# bbtc-relays.net
KiCad netlist of a schematic drawn in EAGLE
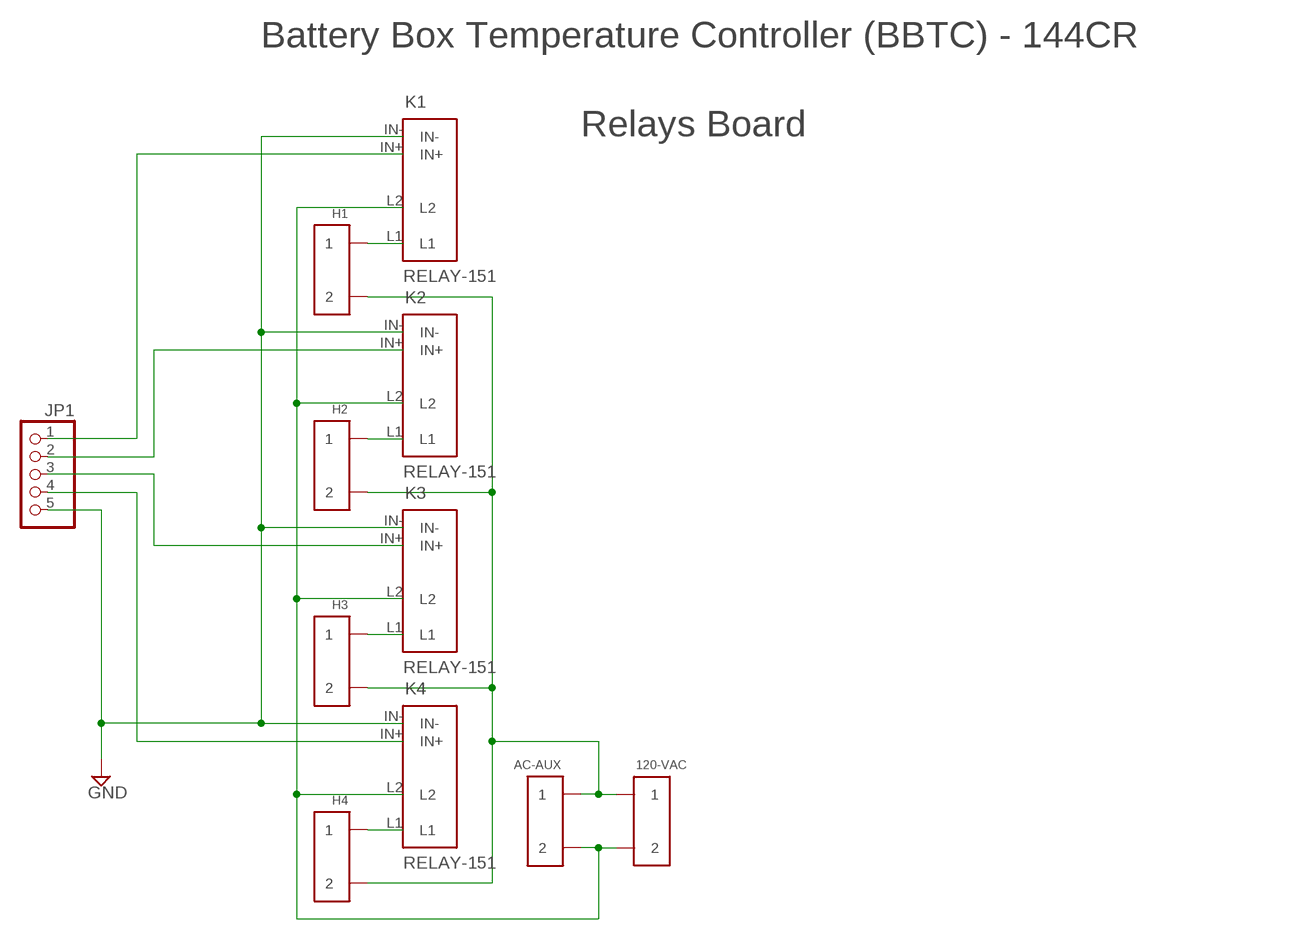
[diagram p0: schematic, sheet 1]

(export (version "E")
  (design (tool "Eeschema 10.0.6"))
  (components
    (comp (ref "120-VAC")
      (value "SCREW-CLAMP-906")
      (footprint "eagle-import:SCREW-CLAMP-906")
      (libsource (lib "eagle-import") (part "SCREW-CLAMP-906"))
    )
    (comp (ref "AC-AUX")
      (value "SCREW-CLAMP-909")
      (footprint "eagle-import:SCREW-CLAMP-909")
      (libsource (lib "eagle-import") (part "SCREW-CLAMP-909"))
    )
    (comp (ref "H1")
      (value "SCREW-CLAMP-906")
      (footprint "eagle-import:SCREW-CLAMP-906")
      (libsource (lib "eagle-import") (part "SCREW-CLAMP-906"))
    )
    (comp (ref "H2")
      (value "SCREW-CLAMP-906")
      (footprint "eagle-import:SCREW-CLAMP-906")
      (libsource (lib "eagle-import") (part "SCREW-CLAMP-906"))
    )
    (comp (ref "H3")
      (value "SCREW-CLAMP-906")
      (footprint "eagle-import:SCREW-CLAMP-906")
      (libsource (lib "eagle-import") (part "SCREW-CLAMP-906"))
    )
    (comp (ref "H4")
      (value "SCREW-CLAMP-906")
      (footprint "eagle-import:SCREW-CLAMP-906")
      (libsource (lib "eagle-import") (part "SCREW-CLAMP-906"))
    )
    (comp (ref "JP1")
      (value "PINHD-1X5")
      (footprint "eagle-import:1X05")
      (libsource (lib "eagle-import") (part "PINHD-1X5"))
    )
    (comp (ref "K1")
      (value "RELAY-151")
      (footprint "eagle-import:RELAY-151")
      (libsource (lib "eagle-import") (part "RELAY-151"))
    )
    (comp (ref "K2")
      (value "RELAY-151")
      (footprint "eagle-import:RELAY-151")
      (libsource (lib "eagle-import") (part "RELAY-151"))
    )
    (comp (ref "K3")
      (value "RELAY-151")
      (footprint "eagle-import:RELAY-151")
      (libsource (lib "eagle-import") (part "RELAY-151"))
    )
    (comp (ref "K4")
      (value "RELAY-151")
      (footprint "eagle-import:RELAY-151")
      (libsource (lib "eagle-import") (part "RELAY-151"))
    )
  )
  (nets
    (net (code "1") (name "GND") (class "Default")
      (node (ref "JP1") (pin "5") (pinfunction "5_5") (pintype "passive"))
      (node (ref "K1") (pin "IN-") (pinfunction "IN-_IN-") (pintype "bidirectional"))
      (node (ref "K2") (pin "IN-") (pinfunction "IN-_IN-") (pintype "bidirectional"))
      (node (ref "K3") (pin "IN-") (pinfunction "IN-_IN-") (pintype "bidirectional"))
      (node (ref "K4") (pin "IN-") (pinfunction "IN-_IN-") (pintype "bidirectional"))
    )
    (net (code "2") (name "Net-(120-VAC-Pad1)") (class "Default")
      (node (ref "120-VAC") (pin "1") (pinfunction "1_1") (pintype "bidirectional"))
      (node (ref "AC-AUX") (pin "1") (pinfunction "1_1") (pintype "bidirectional"))
      (node (ref "H1") (pin "2") (pinfunction "2_2") (pintype "bidirectional"))
      (node (ref "H2") (pin "2") (pinfunction "2_2") (pintype "bidirectional"))
      (node (ref "H3") (pin "2") (pinfunction "2_2") (pintype "bidirectional"))
      (node (ref "H4") (pin "2") (pinfunction "2_2") (pintype "bidirectional"))
    )
    (net (code "3") (name "Net-(120-VAC-Pad2)") (class "Default")
      (node (ref "120-VAC") (pin "2") (pinfunction "2_2") (pintype "bidirectional"))
      (node (ref "AC-AUX") (pin "2") (pinfunction "2_2") (pintype "bidirectional"))
      (node (ref "K1") (pin "L2") (pinfunction "L2_L2") (pintype "bidirectional"))
      (node (ref "K2") (pin "L2") (pinfunction "L2_L2") (pintype "bidirectional"))
      (node (ref "K3") (pin "L2") (pinfunction "L2_L2") (pintype "bidirectional"))
      (node (ref "K4") (pin "L2") (pinfunction "L2_L2") (pintype "bidirectional"))
    )
    (net (code "4") (name "Net-(H1-Pad1)") (class "Default")
      (node (ref "H1") (pin "1") (pinfunction "1_1") (pintype "bidirectional"))
      (node (ref "K1") (pin "L1") (pinfunction "L1_L1") (pintype "bidirectional"))
    )
    (net (code "5") (name "Net-(H2-Pad1)") (class "Default")
      (node (ref "H2") (pin "1") (pinfunction "1_1") (pintype "bidirectional"))
      (node (ref "K2") (pin "L1") (pinfunction "L1_L1") (pintype "bidirectional"))
    )
    (net (code "6") (name "Net-(H3-Pad1)") (class "Default")
      (node (ref "H3") (pin "1") (pinfunction "1_1") (pintype "bidirectional"))
      (node (ref "K3") (pin "L1") (pinfunction "L1_L1") (pintype "bidirectional"))
    )
    (net (code "7") (name "Net-(H4-Pad1)") (class "Default")
      (node (ref "H4") (pin "1") (pinfunction "1_1") (pintype "bidirectional"))
      (node (ref "K4") (pin "L1") (pinfunction "L1_L1") (pintype "bidirectional"))
    )
    (net (code "8") (name "Net-(JP1-Pad1)") (class "Default")
      (node (ref "JP1") (pin "1") (pinfunction "1_1") (pintype "passive"))
      (node (ref "K1") (pin "IN+") (pinfunction "IN+_IN+") (pintype "bidirectional"))
    )
    (net (code "9") (name "Net-(JP1-Pad2)") (class "Default")
      (node (ref "JP1") (pin "2") (pinfunction "2_2") (pintype "passive"))
      (node (ref "K2") (pin "IN+") (pinfunction "IN+_IN+") (pintype "bidirectional"))
    )
    (net (code "10") (name "Net-(JP1-Pad3)") (class "Default")
      (node (ref "JP1") (pin "3") (pinfunction "3_3") (pintype "passive"))
      (node (ref "K3") (pin "IN+") (pinfunction "IN+_IN+") (pintype "bidirectional"))
    )
    (net (code "11") (name "Net-(JP1-Pad4)") (class "Default")
      (node (ref "JP1") (pin "4") (pinfunction "4_4") (pintype "passive"))
      (node (ref "K4") (pin "IN+") (pinfunction "IN+_IN+") (pintype "bidirectional"))
    )
  )
)
